# ta_-sch_ma.net
KiCad netlist of a schematic drawn in EAGLE
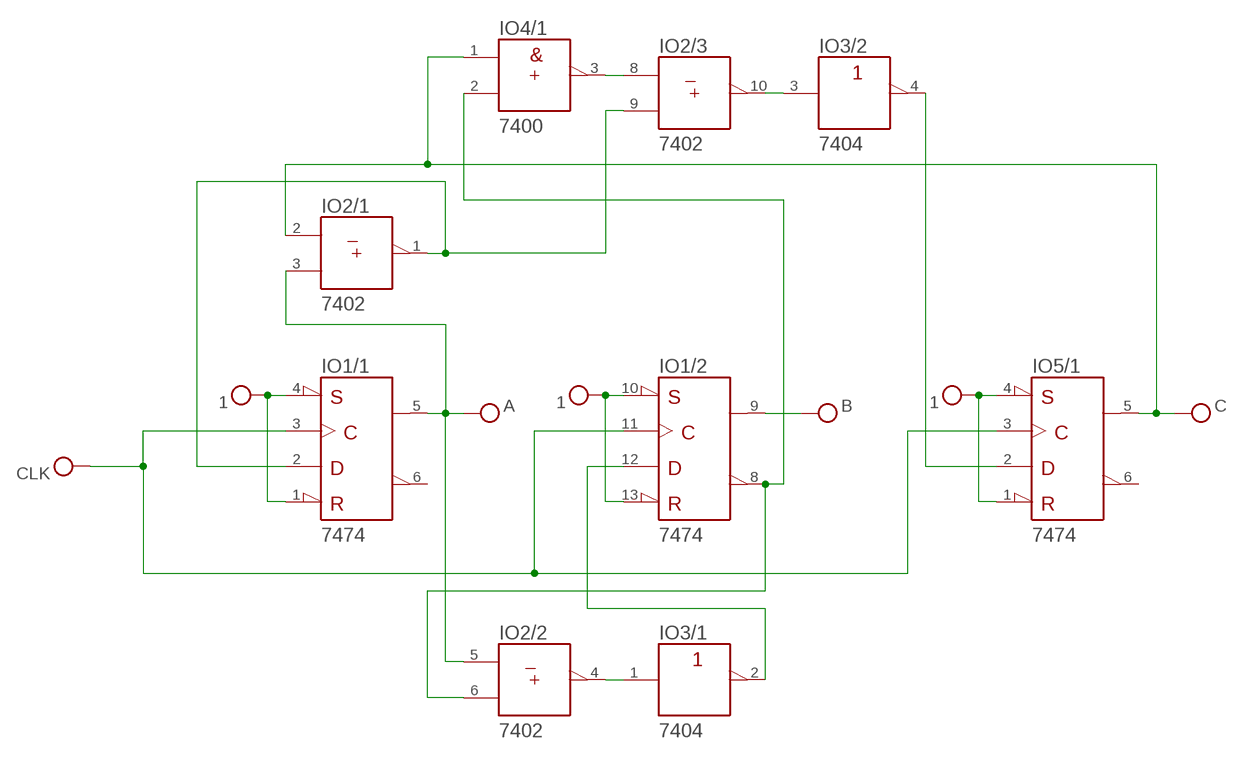
[diagram p0: schematic, sheet 1]

(export (version "E")
  (design (tool "Eeschema 10.0.6"))
  (components
    (comp (ref "IO1")
      (value "7474")
      (footprint "eagle-import:DIL14")
      (libsource (lib "eagle-import") (part "7474N"))
    )
    (comp (ref "IO2")
      (value "7402")
      (footprint "eagle-import:DIL14")
      (libsource (lib "eagle-import") (part "7402N"))
    )
    (comp (ref "IO3")
      (value "7404")
      (footprint "eagle-import:DIL14")
      (libsource (lib "eagle-import") (part "7404N"))
    )
    (comp (ref "IO4")
      (value "7400")
      (footprint "eagle-import:DIL14")
      (libsource (lib "eagle-import") (part "7400N"))
    )
    (comp (ref "IO5")
      (value "7474")
      (footprint "eagle-import:DIL14")
      (libsource (lib "eagle-import") (part "7474N"))
    )
  )
  (nets
    (net (code "1") (name "1") (class "Default")
      (node (ref "IO1") (pin "1") (pinfunction "~{CLR}_1") (pintype "input"))
      (node (ref "IO1") (pin "10") (pinfunction "~{PRE}_10") (pintype "input"))
      (node (ref "IO1") (pin "11") (pinfunction "CLK_11") (pintype "input"))
      (node (ref "IO1") (pin "13") (pinfunction "~{CLR}_13") (pintype "input"))
      (node (ref "IO1") (pin "3") (pinfunction "CLK_3") (pintype "input"))
      (node (ref "IO1") (pin "4") (pinfunction "~{PRE}_4") (pintype "input"))
      (node (ref "IO1") (pin "5") (pinfunction "Q_5") (pintype "output"))
      (node (ref "IO1") (pin "9") (pinfunction "Q_9") (pintype "output"))
      (node (ref "IO2") (pin "2") (pinfunction "A_2") (pintype "input"))
      (node (ref "IO2") (pin "3") (pinfunction "B_3") (pintype "input"))
      (node (ref "IO2") (pin "5") (pinfunction "A_5") (pintype "input"))
      (node (ref "IO4") (pin "1") (pinfunction "A_1") (pintype "input"))
      (node (ref "IO5") (pin "1") (pinfunction "~{CLR}_1") (pintype "input"))
      (node (ref "IO5") (pin "3") (pinfunction "CLK_3") (pintype "input"))
      (node (ref "IO5") (pin "4") (pinfunction "~{PRE}_4") (pintype "input"))
      (node (ref "IO5") (pin "5") (pinfunction "Q_5") (pintype "output"))
    )
    (net (code "2") (name "Net-(IO1C-D)") (class "Default")
      (node (ref "IO1") (pin "2") (pinfunction "D_2") (pintype "input"))
      (node (ref "IO2") (pin "1") (pinfunction "Y_1") (pintype "output"))
      (node (ref "IO2") (pin "9") (pinfunction "B_9") (pintype "input"))
    )
    (net (code "3") (name "Net-(IO1D-D)") (class "Default")
      (node (ref "IO1") (pin "12") (pinfunction "D_12") (pintype "input"))
      (node (ref "IO3") (pin "2") (pinfunction "Y_2") (pintype "output"))
    )
    (net (code "4") (name "Net-(IO1D-~{Q})") (class "Default")
      (node (ref "IO1") (pin "8") (pinfunction "~{Q}_8") (pintype "output"))
      (node (ref "IO2") (pin "6") (pinfunction "B_6") (pintype "input"))
      (node (ref "IO4") (pin "2") (pinfunction "B_2") (pintype "input"))
    )
    (net (code "5") (name "Net-(IO2D-Y)") (class "Default")
      (node (ref "IO2") (pin "4") (pinfunction "Y_4") (pintype "output"))
      (node (ref "IO3") (pin "1") (pinfunction "A_1") (pintype "input"))
    )
    (net (code "6") (name "Net-(IO2E-A)") (class "Default")
      (node (ref "IO2") (pin "8") (pinfunction "A_8") (pintype "input"))
      (node (ref "IO4") (pin "3") (pinfunction "Y_3") (pintype "output"))
    )
    (net (code "7") (name "Net-(IO2E-Y)") (class "Default")
      (node (ref "IO2") (pin "10") (pinfunction "Y_10") (pintype "output"))
      (node (ref "IO3") (pin "3") (pinfunction "A_3") (pintype "input"))
    )
    (net (code "8") (name "Net-(IO3D-Y)") (class "Default")
      (node (ref "IO3") (pin "4") (pinfunction "Y_4") (pintype "output"))
      (node (ref "IO5") (pin "2") (pinfunction "D_2") (pintype "input"))
    )
    (net (code "9") (name "unconnected-(IO1C-~{Q}-Pad6)") (class "Default")
      (node (ref "IO1") (pin "6") (pinfunction "~{Q}_6") (pintype "output"))
    )
    (net (code "10") (name "unconnected-(IO5C-~{Q}-Pad6)") (class "Default")
      (node (ref "IO5") (pin "6") (pinfunction "~{Q}_6") (pintype "output"))
    )
  )
)
